# PaxInstrument-T400.net
KiCad netlist of a schematic drawn in EAGLE
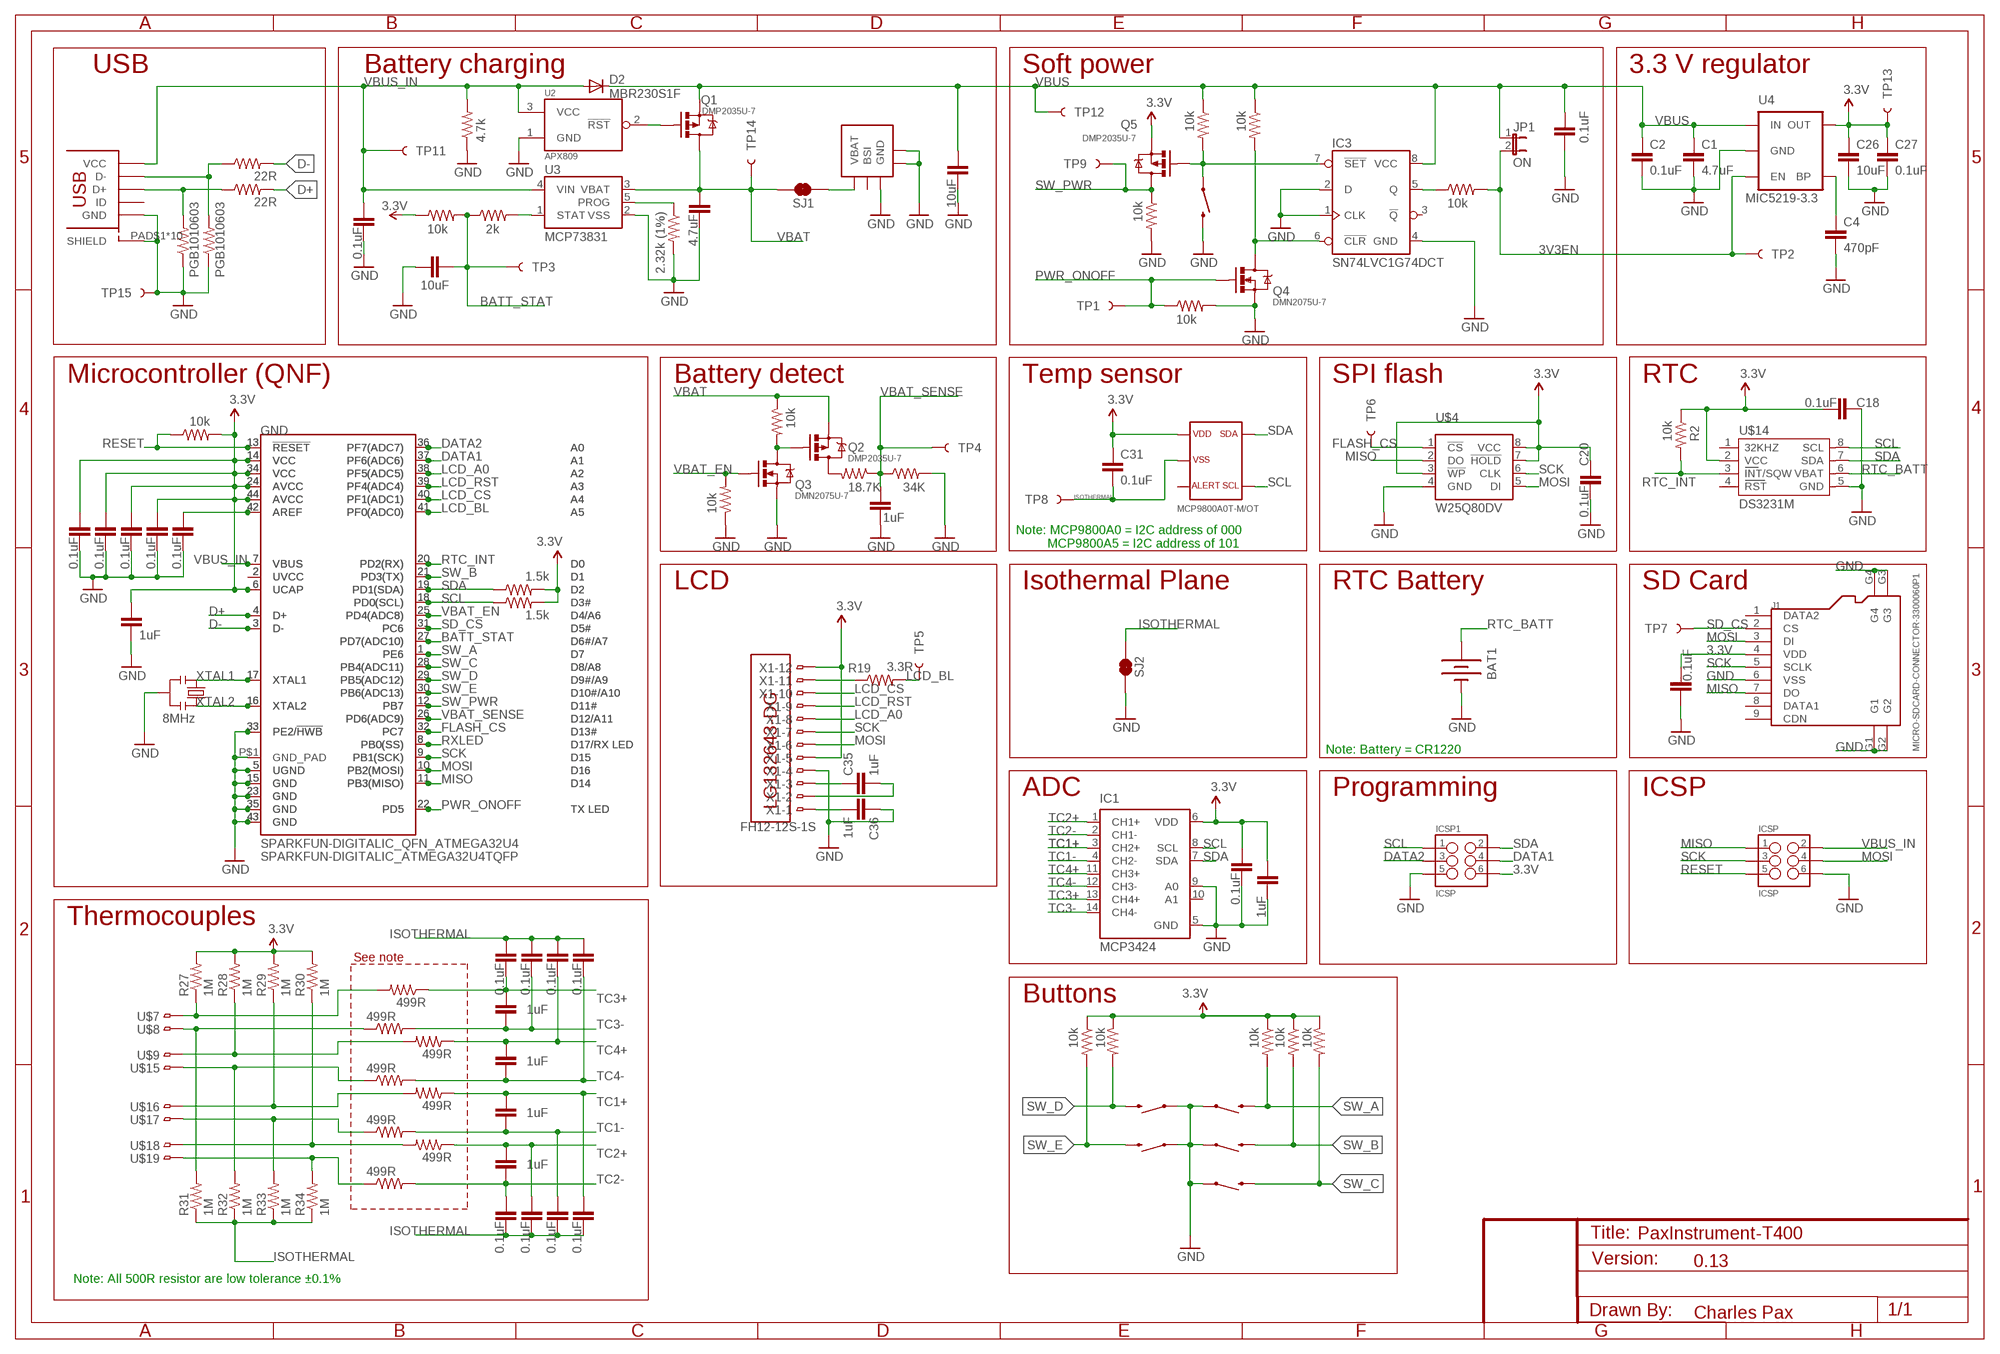
[diagram p0: schematic, sheet 1]

(export (version "E")
  (design (tool "Eeschema 10.0.6"))
  (components
    (comp (ref "BAT1")
      (value "BATTERY12MM")
      (footprint "eagle-import:BATTCON_12MM")
      (fields (field (name "MF") "Keystone Electronics") (field (name "MPN") "3000TR"))
      (libsource (lib "eagle-import") (part "BATTERY12MM"))
    )
    (comp (ref "C1")
      (value "4.7uF")
      (footprint "eagle-import:SPARKFUN-CAPACITORS_0603-CAP")
      (libsource (lib "eagle-import") (part "SPARKFUN-CAPACITORS_CAP0603-CAP"))
    )
    (comp (ref "C2")
      (value "0.1uF")
      (footprint "eagle-import:SPARKFUN-CAPACITORS_0603-CAP")
      (libsource (lib "eagle-import") (part "SPARKFUN-CAPACITORS_CAP0603-CAP"))
    )
    (comp (ref "C3")
      (value "0.1uF")
      (footprint "eagle-import:SPARKFUN-CAPACITORS_0603-CAP")
      (libsource (lib "eagle-import") (part "SPARKFUN-CAPACITORS_CAP0603-CAP"))
    )
    (comp (ref "C4")
      (value "470pF")
      (footprint "eagle-import:SPARKFUN-CAPACITORS_0603-CAP")
      (libsource (lib "eagle-import") (part "SPARKFUN-CAPACITORS_CAP0603-CAP"))
    )
    (comp (ref "C5")
      (value "0.1uF")
      (footprint "eagle-import:SPARKFUN-CAPACITORS_0603-CAP")
      (libsource (lib "eagle-import") (part "SPARKFUN-CAPACITORS_CAP0603-CAP"))
    )
    (comp (ref "C6")
      (value "0.1uF")
      (footprint "eagle-import:SPARKFUN-CAPACITORS_0603-CAP")
      (libsource (lib "eagle-import") (part "SPARKFUN-CAPACITORS_CAP0603-CAP"))
    )
    (comp (ref "C7")
      (value "1uF")
      (footprint "eagle-import:SPARKFUN-CAPACITORS_0603-CAP")
      (libsource (lib "eagle-import") (part "SPARKFUN-CAPACITORS_CAP0603-CAP"))
    )
    (comp (ref "C8")
      (value "1uF")
      (footprint "eagle-import:SPARKFUN-CAPACITORS_0603-CAP")
      (libsource (lib "eagle-import") (part "SPARKFUN-CAPACITORS_CAP0603-CAP"))
    )
    (comp (ref "C9")
      (value "4.7uF")
      (footprint "eagle-import:SPARKFUN-CAPACITORS_0603-CAP")
      (libsource (lib "eagle-import") (part "SPARKFUN-CAPACITORS_CAP0603-CAP"))
    )
    (comp (ref "C10")
      (value "1uF")
      (footprint "eagle-import:SPARKFUN-CAPACITORS_0603-CAP")
      (libsource (lib "eagle-import") (part "SPARKFUN-CAPACITORS_CAP0603-CAP"))
    )
    (comp (ref "C11")
      (value "1uF")
      (footprint "eagle-import:SPARKFUN-CAPACITORS_0603-CAP")
      (libsource (lib "eagle-import") (part "SPARKFUN-CAPACITORS_CAP0603-CAP"))
    )
    (comp (ref "C12")
      (value "10uF")
      (footprint "eagle-import:SPARKFUN-CAPACITORS_0603-CAP")
      (libsource (lib "eagle-import") (part "SPARKFUN-CAPACITORS_CAP0603-CAP"))
    )
    (comp (ref "C13")
      (value "0.1uF")
      (footprint "eagle-import:SPARKFUN-CAPACITORS_0603-CAP")
      (libsource (lib "eagle-import") (part "SPARKFUN-CAPACITORS_CAP0603-CAP"))
    )
    (comp (ref "C14")
      (value "0.1uF")
      (footprint "eagle-import:SPARKFUN-CAPACITORS_0603-CAP")
      (libsource (lib "eagle-import") (part "SPARKFUN-CAPACITORS_CAP0603-CAP"))
    )
    (comp (ref "C15")
      (value "0.1uF")
      (footprint "eagle-import:SPARKFUN-CAPACITORS_0603-CAP")
      (libsource (lib "eagle-import") (part "SPARKFUN-CAPACITORS_CAP0603-CAP"))
    )
    (comp (ref "C16")
      (value "0.1uF")
      (footprint "eagle-import:SPARKFUN-CAPACITORS_0603-CAP")
      (libsource (lib "eagle-import") (part "SPARKFUN-CAPACITORS_CAP0603-CAP"))
    )
    (comp (ref "C17")
      (value "0.1uF")
      (footprint "eagle-import:SPARKFUN-CAPACITORS_0603-CAP")
      (libsource (lib "eagle-import") (part "SPARKFUN-CAPACITORS_CAP0603-CAP"))
    )
    (comp (ref "C18")
      (value "0.1uF")
      (footprint "eagle-import:SPARKFUN-CAPACITORS_0603-CAP")
      (libsource (lib "eagle-import") (part "SPARKFUN-CAPACITORS_CAP0603-CAP"))
    )
    (comp (ref "C19")
      (value "1uF")
      (footprint "eagle-import:SPARKFUN-CAPACITORS_0603-CAP")
      (libsource (lib "eagle-import") (part "SPARKFUN-CAPACITORS_CAP0603-CAP"))
    )
    (comp (ref "C20")
      (value "0.1uF")
      (footprint "eagle-import:SPARKFUN-CAPACITORS_0603-CAP")
      (libsource (lib "eagle-import") (part "SPARKFUN-CAPACITORS_CAP0603-CAP"))
    )
    (comp (ref "C21")
      (value "0.1uF")
      (footprint "eagle-import:SPARKFUN-CAPACITORS_0603-CAP")
      (libsource (lib "eagle-import") (part "SPARKFUN-CAPACITORS_CAP0603-CAP"))
    )
    (comp (ref "C22")
      (value "10uF")
      (footprint "eagle-import:SPARKFUN-CAPACITORS_0603-CAP")
      (libsource (lib "eagle-import") (part "SPARKFUN-CAPACITORS_CAP0603-CAP"))
    )
    (comp (ref "C23")
      (value "1uF")
      (footprint "eagle-import:SPARKFUN-CAPACITORS_0603-CAP")
      (libsource (lib "eagle-import") (part "SPARKFUN-CAPACITORS_CAP0603-CAP"))
    )
    (comp (ref "C24")
      (value "0.1uF")
      (footprint "eagle-import:SPARKFUN-CAPACITORS_0603-CAP")
      (libsource (lib "eagle-import") (part "SPARKFUN-CAPACITORS_CAP0603-CAP"))
    )
    (comp (ref "C25")
      (value "0.1uF")
      (footprint "eagle-import:SPARKFUN-CAPACITORS_0603-CAP")
      (libsource (lib "eagle-import") (part "SPARKFUN-CAPACITORS_CAP0603-CAP"))
    )
    (comp (ref "C26")
      (value "10uF")
      (footprint "eagle-import:SPARKFUN-CAPACITORS_0603-CAP")
      (libsource (lib "eagle-import") (part "SPARKFUN-CAPACITORS_CAP0603-CAP"))
    )
    (comp (ref "C27")
      (value "0.1uF")
      (footprint "eagle-import:SPARKFUN-CAPACITORS_0603-CAP")
      (libsource (lib "eagle-import") (part "SPARKFUN-CAPACITORS_CAP0603-CAP"))
    )
    (comp (ref "C28")
      (value "0.1uF")
      (footprint "eagle-import:SPARKFUN-CAPACITORS_0603-CAP")
      (libsource (lib "eagle-import") (part "SPARKFUN-CAPACITORS_CAP0603-CAP"))
    )
    (comp (ref "C29")
      (value "0.1uF")
      (footprint "eagle-import:SPARKFUN-CAPACITORS_0603-CAP")
      (libsource (lib "eagle-import") (part "SPARKFUN-CAPACITORS_CAP0603-CAP"))
    )
    (comp (ref "C30")
      (value "1uF")
      (footprint "eagle-import:SPARKFUN-CAPACITORS_0603-CAP")
      (libsource (lib "eagle-import") (part "SPARKFUN-CAPACITORS_CAP0603-CAP"))
    )
    (comp (ref "C31")
      (value "0.1uF")
      (footprint "eagle-import:SPARKFUN-CAPACITORS_0603-CAP")
      (libsource (lib "eagle-import") (part "SPARKFUN-CAPACITORS_CAP0603-CAP"))
    )
    (comp (ref "C32")
      (value "0.1uF")
      (footprint "eagle-import:SPARKFUN-CAPACITORS_0603-CAP")
      (libsource (lib "eagle-import") (part "SPARKFUN-CAPACITORS_CAP0603-CAP"))
    )
    (comp (ref "C33")
      (value "0.1uF")
      (footprint "eagle-import:SPARKFUN-CAPACITORS_0603-CAP")
      (libsource (lib "eagle-import") (part "SPARKFUN-CAPACITORS_CAP0603-CAP"))
    )
    (comp (ref "C34")
      (value "0.1uF")
      (footprint "eagle-import:SPARKFUN-CAPACITORS_0603-CAP")
      (libsource (lib "eagle-import") (part "SPARKFUN-CAPACITORS_CAP0603-CAP"))
    )
    (comp (ref "C35")
      (value "1uF")
      (footprint "eagle-import:SPARKFUN-CAPACITORS_0603-CAP")
      (libsource (lib "eagle-import") (part "SPARKFUN-CAPACITORS_CAP0603-CAP"))
    )
    (comp (ref "C36")
      (value "1uF")
      (footprint "eagle-import:SPARKFUN-CAPACITORS_0603-CAP")
      (libsource (lib "eagle-import") (part "SPARKFUN-CAPACITORS_CAP0603-CAP"))
    )
    (comp (ref "C37")
      (value "0.1uF")
      (footprint "eagle-import:SPARKFUN-CAPACITORS_0603-CAP")
      (libsource (lib "eagle-import") (part "SPARKFUN-CAPACITORS_CAP0603-CAP"))
    )
    (comp (ref "D2")
      (value "MBR230S1F")
      (footprint "eagle-import:SOD123")
      (fields (field (name "MF") "DIODES INC") (field (name "MPN") "MBR230S1F-7"))
      (libsource (lib "eagle-import") (part "SPARKFUN-DISCRETESEMI_DIODESOD123SOD123"))
    )
    (comp (ref "GND")
      (value "SPARKFUN-DIGITALIC_QFN_ATMEGA32U4")
      (footprint "eagle-import:SPARKFUN-DIGITALIC_SPARKFUN-DIGITALIC_QFN-44")
      (fields (field (name "MF") "Atmel") (field (name "MPN") "ATMEGA32U4-MU"))
      (libsource (lib "eagle-import") (part "SPARKFUN-DIGITALIC_QFN_ATMEGA32U4"))
    )
    (comp (ref "IC1")
      (value "MCP3424")
      (footprint "eagle-import:SO14")
      (fields (field (name "MF") "Microchip Technology") (field (name "MPN") "MCP3424-E/SL"))
      (libsource (lib "eagle-import") (part "MCP3424"))
    )
    (comp (ref "IC3")
      (value "SN74LVC1G74DCT")
      (footprint "eagle-import:SSOP8")
      (fields (field (name "MF") "Texas Instruments") (field (name "MPN") "SN74LVC1G74DCTR "))
      (libsource (lib "eagle-import") (part "SN74LVC1G74DCT"))
    )
    (comp (ref "ICSP")
      (value "ICSP")
      (footprint "eagle-import:SPARKFUN-CONNECTORS_2X3_SMT_POSTS_PAXINSTRUMENT")
      (fields (field (name "MF") "FCI") (field (name "MPN") "95278-101A06LF"))
      (libsource (lib "eagle-import") (part "SPARKFUN-CONNECTORS_M03X2PAX"))
    )
    (comp (ref "ICSP1")
      (value "ICSP")
      (footprint "eagle-import:SPARKFUN-CONNECTORS_2X3_SMT_POSTS_PAXINSTRUMENT")
      (fields (field (name "MF") "FCI") (field (name "MPN") "95278-101A06LF"))
      (libsource (lib "eagle-import") (part "SPARKFUN-CONNECTORS_M03X2PAX"))
    )
    (comp (ref "J1")
      (value "MICRO-SDCARD-CONNECTOR-3300060P1")
      (footprint "eagle-import:9P-SMD-W-RING")
      (fields (field (name "MF") "SUNTECH") (field (name "MPN") "ST-TF-003A"))
      (libsource (lib "eagle-import") (part "MICRO-SDCARD-CONNECTOR-3300060P1"))
    )
    (comp (ref "JP1")
      (value "ON")
      (footprint "eagle-import:SJ_2S-NO")
      (libsource (lib "eagle-import") (part "JUMPER-2SMD-NO"))
    )
    (comp (ref "Q1")
      (value "DMP2035U-7")
      (footprint "eagle-import:SOT23")
      (fields (field (name "MF") "DIODES INC"))
      (libsource (lib "eagle-import") (part "MOSFET-PCHANNELSMT"))
    )
    (comp (ref "Q2")
      (value "DMP2035U-7")
      (footprint "eagle-import:SOT23")
      (fields (field (name "MF") "DIODES INC"))
      (libsource (lib "eagle-import") (part "MOSFET-PCHANNELSMT"))
    )
    (comp (ref "Q3")
      (value "DMN2075U-7")
      (footprint "eagle-import:SOT23")
      (fields (field (name "MF") "DIODES INC") (field (name "MPN") "DMN2075U-7 "))
      (libsource (lib "eagle-import") (part "MOSFET-NCHANNELSMT"))
    )
    (comp (ref "Q4")
      (value "DMN2075U-7")
      (footprint "eagle-import:SOT23")
      (fields (field (name "MF") "DIODES INC") (field (name "MPN") "DMN2075U-7 "))
      (libsource (lib "eagle-import") (part "MOSFET-NCHANNELSMT"))
    )
    (comp (ref "Q5")
      (value "DMP2035U-7")
      (footprint "eagle-import:SOT23")
      (fields (field (name "MF") "DIODES INC"))
      (libsource (lib "eagle-import") (part "MOSFET-PCHANNELSMT"))
    )
    (comp (ref "R1")
      (value "10k")
      (footprint "eagle-import:SPARKFUN-RESISTORS_0603-RES")
      (libsource (lib "eagle-import") (part "SPARKFUN-RESISTORS_RESISTOR0603-RES"))
    )
    (comp (ref "R2")
      (value "10k")
      (footprint "eagle-import:SPARKFUN-RESISTORS_0603-RES")
      (libsource (lib "eagle-import") (part "SPARKFUN-RESISTORS_RESISTOR0603-RES"))
    )
    (comp (ref "R3")
      (value "2.32k (1%)")
      (footprint "eagle-import:SPARKFUN-RESISTORS_0603-RES")
      (libsource (lib "eagle-import") (part "SPARKFUN-RESISTORS_RESISTOR0603-RES"))
    )
    (comp (ref "R4")
      (value "10k")
      (footprint "eagle-import:SPARKFUN-RESISTORS_0603-RES")
      (libsource (lib "eagle-import") (part "SPARKFUN-RESISTORS_RESISTOR0603-RES"))
    )
    (comp (ref "R5")
      (value "10k")
      (footprint "eagle-import:SPARKFUN-RESISTORS_0603-RES")
      (libsource (lib "eagle-import") (part "SPARKFUN-RESISTORS_RESISTOR0603-RES"))
    )
    (comp (ref "R6")
      (value "10k")
      (footprint "eagle-import:SPARKFUN-RESISTORS_0603-RES")
      (libsource (lib "eagle-import") (part "SPARKFUN-RESISTORS_RESISTOR0603-RES"))
    )
    (comp (ref "R7")
      (value "10k")
      (footprint "eagle-import:SPARKFUN-RESISTORS_0603-RES")
      (libsource (lib "eagle-import") (part "SPARKFUN-RESISTORS_RESISTOR0603-RES"))
    )
    (comp (ref "R8")
      (value "10k")
      (footprint "eagle-import:SPARKFUN-RESISTORS_0603-RES")
      (libsource (lib "eagle-import") (part "SPARKFUN-RESISTORS_RESISTOR0603-RES"))
    )
    (comp (ref "R9")
      (value "22R")
      (footprint "eagle-import:SPARKFUN-RESISTORS_0603-RES")
      (libsource (lib "eagle-import") (part "SPARKFUN-RESISTORS_RESISTOR0603-RES"))
    )
    (comp (ref "R10")
      (value "22R")
      (footprint "eagle-import:SPARKFUN-RESISTORS_0603-RES")
      (libsource (lib "eagle-import") (part "SPARKFUN-RESISTORS_RESISTOR0603-RES"))
    )
    (comp (ref "R11")
      (value "10k")
      (footprint "eagle-import:SPARKFUN-RESISTORS_0603-RES")
      (libsource (lib "eagle-import") (part "SPARKFUN-RESISTORS_RESISTOR0603-RES"))
    )
    (comp (ref "R12")
      (value "10k")
      (footprint "eagle-import:SPARKFUN-RESISTORS_0603-RES")
      (libsource (lib "eagle-import") (part "SPARKFUN-RESISTORS_RESISTOR0603-RES"))
    )
    (comp (ref "R13")
      (value "1.5k")
      (footprint "eagle-import:SPARKFUN-RESISTORS_0603-RES")
      (libsource (lib "eagle-import") (part "SPARKFUN-RESISTORS_RESISTOR0603-RES"))
    )
    (comp (ref "R14")
      (value "1.5k")
      (footprint "eagle-import:SPARKFUN-RESISTORS_0603-RES")
      (libsource (lib "eagle-import") (part "SPARKFUN-RESISTORS_RESISTOR0603-RES"))
    )
    (comp (ref "R15")
      (value "10k")
      (footprint "eagle-import:SPARKFUN-RESISTORS_0603-RES")
      (libsource (lib "eagle-import") (part "SPARKFUN-RESISTORS_RESISTOR0603-RES"))
    )
    (comp (ref "R16")
      (value "10k")
      (footprint "eagle-import:SPARKFUN-RESISTORS_0603-RES")
      (libsource (lib "eagle-import") (part "SPARKFUN-RESISTORS_RESISTOR0603-RES"))
    )
    (comp (ref "R17")
      (value "2k")
      (footprint "eagle-import:SPARKFUN-RESISTORS_0603-RES")
      (libsource (lib "eagle-import") (part "SPARKFUN-RESISTORS_RESISTOR0603-RES"))
    )
    (comp (ref "R18")
      (value "10k")
      (footprint "eagle-import:SPARKFUN-RESISTORS_0603-RES")
      (libsource (lib "eagle-import") (part "SPARKFUN-RESISTORS_RESISTOR0603-RES"))
    )
    (comp (ref "R19")
      (value "3.3R")
      (footprint "eagle-import:SPARKFUN-RESISTORS_0603-RES")
      (libsource (lib "eagle-import") (part "SPARKFUN-RESISTORS_RESISTOR0603-RES"))
    )
    (comp (ref "R20")
      (value "18.7K")
      (footprint "eagle-import:SPARKFUN-RESISTORS_0603-RES")
      (libsource (lib "eagle-import") (part "SPARKFUN-RESISTORS_RESISTOR0603-RES"))
    )
    (comp (ref "R21")
      (value "10k")
      (footprint "eagle-import:SPARKFUN-RESISTORS_0603-RES")
      (libsource (lib "eagle-import") (part "SPARKFUN-RESISTORS_RESISTOR0603-RES"))
    )
    (comp (ref "R22")
      (value "10k")
      (footprint "eagle-import:SPARKFUN-RESISTORS_0603-RES")
      (libsource (lib "eagle-import") (part "SPARKFUN-RESISTORS_RESISTOR0603-RES"))
    )
    (comp (ref "R23")
      (value "10k")
      (footprint "eagle-import:SPARKFUN-RESISTORS_0603-RES")
      (libsource (lib "eagle-import") (part "SPARKFUN-RESISTORS_RESISTOR0603-RES"))
    )
    (comp (ref "R24")
      (value "34K")
      (footprint "eagle-import:SPARKFUN-RESISTORS_0603-RES")
      (libsource (lib "eagle-import") (part "SPARKFUN-RESISTORS_RESISTOR0603-RES"))
    )
    (comp (ref "R25")
      (value "4.7k")
      (footprint "eagle-import:SPARKFUN-RESISTORS_0603-RES")
      (libsource (lib "eagle-import") (part "SPARKFUN-RESISTORS_RESISTOR0603-RES"))
    )
    (comp (ref "R27")
      (value "1M")
      (footprint "eagle-import:SPARKFUN-RESISTORS_0603-RES")
      (libsource (lib "eagle-import") (part "SPARKFUN-RESISTORS_RESISTOR0603-RES"))
    )
    (comp (ref "R28")
      (value "1M")
      (footprint "eagle-import:SPARKFUN-RESISTORS_0603-RES")
      (libsource (lib "eagle-import") (part "SPARKFUN-RESISTORS_RESISTOR0603-RES"))
    )
    (comp (ref "R29")
      (value "1M")
      (footprint "eagle-import:SPARKFUN-RESISTORS_0603-RES")
      (libsource (lib "eagle-import") (part "SPARKFUN-RESISTORS_RESISTOR0603-RES"))
    )
    (comp (ref "R30")
      (value "1M")
      (footprint "eagle-import:SPARKFUN-RESISTORS_0603-RES")
      (libsource (lib "eagle-import") (part "SPARKFUN-RESISTORS_RESISTOR0603-RES"))
    )
    (comp (ref "R31")
      (value "1M")
      (footprint "eagle-import:SPARKFUN-RESISTORS_0603-RES")
      (libsource (lib "eagle-import") (part "SPARKFUN-RESISTORS_RESISTOR0603-RES"))
    )
    (comp (ref "R32")
      (value "1M")
      (footprint "eagle-import:SPARKFUN-RESISTORS_0603-RES")
      (libsource (lib "eagle-import") (part "SPARKFUN-RESISTORS_RESISTOR0603-RES"))
    )
    (comp (ref "R33")
      (value "1M")
      (footprint "eagle-import:SPARKFUN-RESISTORS_0603-RES")
      (libsource (lib "eagle-import") (part "SPARKFUN-RESISTORS_RESISTOR0603-RES"))
    )
    (comp (ref "R34")
      (value "1M")
      (footprint "eagle-import:SPARKFUN-RESISTORS_0603-RES")
      (libsource (lib "eagle-import") (part "SPARKFUN-RESISTORS_RESISTOR0603-RES"))
    )
    (comp (ref "R35")
      (value "499R")
      (footprint "eagle-import:SPARKFUN-RESISTORS_0603-RES")
      (fields (field (name "MF") "Vishay") (field (name "MPN") "TNPW0603499RBEEA"))
      (libsource (lib "eagle-import") (part "SPARKFUN-RESISTORS_RESISTOR0603-RES"))
    )
    (comp (ref "R36")
      (value "499R")
      (footprint "eagle-import:SPARKFUN-RESISTORS_0603-RES")
      (fields (field (name "MF") "Vishay") (field (name "MPN") "TNPW0603499RBEEA"))
      (libsource (lib "eagle-import") (part "SPARKFUN-RESISTORS_RESISTOR0603-RES"))
    )
    (comp (ref "R37")
      (value "499R")
      (footprint "eagle-import:SPARKFUN-RESISTORS_0603-RES")
      (fields (field (name "MF") "Vishay") (field (name "MPN") "TNPW0603499RBEEA"))
      (libsource (lib "eagle-import") (part "SPARKFUN-RESISTORS_RESISTOR0603-RES"))
    )
    (comp (ref "R38")
      (value "499R")
      (footprint "eagle-import:SPARKFUN-RESISTORS_0603-RES")
      (fields (field (name "MF") "Vishay") (field (name "MPN") "TNPW0603499RBEEA"))
      (libsource (lib "eagle-import") (part "SPARKFUN-RESISTORS_RESISTOR0603-RES"))
    )
    (comp (ref "R39")
      (value "499R")
      (footprint "eagle-import:SPARKFUN-RESISTORS_0603-RES")
      (fields (field (name "MF") "Vishay") (field (name "MPN") "TNPW0603499RBEEA"))
      (libsource (lib "eagle-import") (part "SPARKFUN-RESISTORS_RESISTOR0603-RES"))
    )
    (comp (ref "R40")
      (value "499R")
      (footprint "eagle-import:SPARKFUN-RESISTORS_0603-RES")
      (fields (field (name "MF") "Vishay") (field (name "MPN") "TNPW0603499RBEEA"))
      (libsource (lib "eagle-import") (part "SPARKFUN-RESISTORS_RESISTOR0603-RES"))
    )
    (comp (ref "R41")
      (value "499R")
      (footprint "eagle-import:SPARKFUN-RESISTORS_0603-RES")
      (fields (field (name "MF") "Vishay") (field (name "MPN") "TNPW0603499RBEEA"))
      (libsource (lib "eagle-import") (part "SPARKFUN-RESISTORS_RESISTOR0603-RES"))
    )
    (comp (ref "R42")
      (value "499R")
      (footprint "eagle-import:SPARKFUN-RESISTORS_0603-RES")
      (fields (field (name "MF") "Vishay") (field (name "MPN") "TNPW0603499RBEEA"))
      (libsource (lib "eagle-import") (part "SPARKFUN-RESISTORS_RESISTOR0603-RES"))
    )
    (comp (ref "S1")
      (value "SWITCH-MOMENTARY-2SMD")
      (footprint "eagle-import:TACTILE_SWITCH_SMD")
      (fields (field (name "MF") "C&K Components") (field (name "MPN") "RS-187R05A2-DS MT RT"))
      (libsource (lib "eagle-import") (part "SWITCH-MOMENTARY-2SMD"))
    )
    (comp (ref "S2")
      (value "SWITCH-MOMENTARY-2SMD")
      (footprint "eagle-import:TACTILE_SWITCH_SMD")
      (fields (field (name "MF") "C&K Components") (field (name "MPN") "RS-187R05A2-DS MT RT"))
      (libsource (lib "eagle-import") (part "SWITCH-MOMENTARY-2SMD"))
    )
    (comp (ref "S3")
      (value "SWITCH-MOMENTARY-2SMD")
      (footprint "eagle-import:TACTILE_SWITCH_SMD")
      (fields (field (name "MF") "C&K Components") (field (name "MPN") "RS-187R05A2-DS MT RT"))
      (libsource (lib "eagle-import") (part "SWITCH-MOMENTARY-2SMD"))
    )
    (comp (ref "S4")
      (value "SWITCH-MOMENTARY-2SMD")
      (footprint "eagle-import:TACTILE_SWITCH_SMD")
      (fields (field (name "MF") "C&K Components") (field (name "MPN") "RS-187R05A2-DS MT RT"))
      (libsource (lib "eagle-import") (part "SWITCH-MOMENTARY-2SMD"))
    )
    (comp (ref "S5")
      (value "SWITCH-MOMENTARY-2SMD")
      (footprint "eagle-import:TACTILE_SWITCH_SMD")
      (fields (field (name "MF") "C&K Components") (field (name "MPN") "RS-187R05A2-DS MT RT"))
      (libsource (lib "eagle-import") (part "SWITCH-MOMENTARY-2SMD"))
    )
    (comp (ref "S6")
      (value "SWITCH-MOMENTARY-2SMD")
      (footprint "eagle-import:TACTILE_SWITCH_SMD")
      (fields (field (name "MF") "C&K Components") (field (name "MPN") "RS-187R05A2-DS MT RT"))
      (libsource (lib "eagle-import") (part "SWITCH-MOMENTARY-2SMD"))
    )
    (comp (ref "SJ1")
      (value "JUMPER-PAD-2-NC_BY_TRACE")
      (footprint "eagle-import:PAD-JUMPER-2-NC_BY_TRACE_YES_SILK")
      (libsource (lib "eagle-import") (part "JUMPER-PAD-2-NC_BY_TRACE"))
    )
    (comp (ref "SJ2")
      (value "JUMPER-PAD-2-NC_BY_TRACE")
      (footprint "eagle-import:PAD-JUMPER-2-NC_BY_TRACE_YES_SILK")
      (libsource (lib "eagle-import") (part "JUMPER-PAD-2-NC_BY_TRACE"))
    )
    (comp (ref "TP1")
      (value "PWR_ONOFF")
      (footprint "eagle-import:TP_15TH")
      (libsource (lib "eagle-import") (part "TEST-POINTTP_15TH_THRU"))
    )
    (comp (ref "TP2")
      (value "3V3_EN")
      (footprint "eagle-import:TP_15TH")
      (libsource (lib "eagle-import") (part "TEST-POINTTP_15TH_THRU"))
    )
    (comp (ref "TP3")
      (value "BATT_STAT")
      (footprint "eagle-import:TP_15TH")
      (libsource (lib "eagle-import") (part "TEST-POINTTP_15TH_THRU"))
    )
    (comp (ref "TP4")
      (value "VBAT_SENSE")
      (footprint "eagle-import:TP_15TH")
      (libsource (lib "eagle-import") (part "TEST-POINTTP_15TH_THRU"))
    )
    (comp (ref "TP5")
      (value "LCD_BL")
      (footprint "eagle-import:TP_15TH")
      (libsource (lib "eagle-import") (part "TEST-POINTTP_15TH_THRU"))
    )
    (comp (ref "TP6")
      (value "FLASH_CS")
      (footprint "eagle-import:TP_15TH")
      (libsource (lib "eagle-import") (part "TEST-POINTTP_15TH_THRU"))
    )
    (comp (ref "TP7")
      (value "SD_CS")
      (footprint "eagle-import:TP_15TH")
      (libsource (lib "eagle-import") (part "TEST-POINTTP_15TH_THRU"))
    )
    (comp (ref "TP8")
      (value "ISOTHERMAL")
      (footprint "eagle-import:TP_15TH")
      (libsource (lib "eagle-import") (part "TEST-POINTTP_15TH_THRU"))
    )
    (comp (ref "TP9")
      (value "SW_PWR")
      (footprint "eagle-import:TP_15TH")
      (libsource (lib "eagle-import") (part "TEST-POINTTP_15TH_THRU"))
    )
    (comp (ref "TP11")
      (value "VBUS_IN")
      (footprint "eagle-import:TP_15TH")
      (libsource (lib "eagle-import") (part "TEST-POINTTP_15TH_THRU"))
    )
    (comp (ref "TP12")
      (value "VBUS")
      (footprint "eagle-import:TP_15TH")
      (libsource (lib "eagle-import") (part "TEST-POINTTP_15TH_THRU"))
    )
    (comp (ref "TP13")
      (value "3.3V")
      (footprint "eagle-import:TP_15TH")
      (libsource (lib "eagle-import") (part "TEST-POINTTP_15TH_THRU"))
    )
    (comp (ref "TP14")
      (value "VBAT")
      (footprint "eagle-import:TP_15TH")
      (libsource (lib "eagle-import") (part "TEST-POINTTP_15TH_THRU"))
    )
    (comp (ref "TP15")
      (value "GND")
      (footprint "eagle-import:TP_15TH")
      (libsource (lib "eagle-import") (part "TEST-POINTTP_15TH_THRU"))
    )
    (comp (ref "U$1")
      (value "USB_MICROSMT+THRUHULE")
      (footprint "eagle-import:USB_MICRO_THRUHOLE")
      (fields (field (name "MF") "FCI") (field (name "MPN") "10118194-0001LF"))
      (libsource (lib "eagle-import") (part "USB_MICROSMT+THRUHULE"))
    )
    (comp (ref "U$2")
      (value "BL-5C-CONNECTOR")
      (footprint "eagle-import:BL-5C-CONNECTOR")
      (fields (field (name "MPN") "BC-4-3P (77H)"))
      (libsource (lib "eagle-import") (part "BL-5C-CONNECTOR"))
    )
    (comp (ref "U$3")
      (value "SPARKFUN-DIGITALIC_ATMEGA32U4TQFP")
      (footprint "eagle-import:SPARKFUN-DIGITALIC_SPARKFUN-DIGITALIC_TQFP44")
      (fields (field (name "MF") "Atmel") (field (name "MPN") "ATMEGA32U4-AU"))
      (libsource (lib "eagle-import") (part "SPARKFUN-DIGITALIC_ATMEGA32U4TQFP"))
    )
    (comp (ref "U$4")
      (value "W25Q80DV")
      (footprint "eagle-import:CHARLESPAX_SOIC8M")
      (fields (field (name "MF") "Winbond Electronics") (field (name "MPN") "W25Q80DVSSIG-ND"))
      (libsource (lib "eagle-import") (part "W25Q80BV"))
    )
    (comp (ref "U$5")
      (value "LG132643-DG")
      (footprint "eagle-import:LG132643-DG")
      (fields (field (name "MPN") "LG132643-DW"))
      (libsource (lib "eagle-import") (part "LG132643-DG"))
    )
    (comp (ref "U$7")
      (value "TC-MINI-SINGLE")
      (footprint "eagle-import:TC-CLIP-SINGLE")
      (fields (field (name "MF") "Pax Instrument") (field (name "MPN") "Thermo-clip2"))
      (libsource (lib "eagle-import") (part "TC-MINI-SINGLE"))
    )
    (comp (ref "U$8")
      (value "TC-MINI-SINGLE")
      (footprint "eagle-import:TC-CLIP-SINGLE")
      (fields (field (name "MF") "Pax Instrument") (field (name "MPN") "Thermo-clip2"))
      (libsource (lib "eagle-import") (part "TC-MINI-SINGLE"))
    )
    (comp (ref "U$9")
      (value "TC-MINI-SINGLE")
      (footprint "eagle-import:TC-CLIP-SINGLE")
      (fields (field (name "MF") "Pax Instrument") (field (name "MPN") "Thermo-clip2"))
      (libsource (lib "eagle-import") (part "TC-MINI-SINGLE"))
    )
    (comp (ref "U$14")
      (value "DS3231M")
      (footprint "eagle-import:SOIC8")
      (fields (field (name "MF") "Maxim Integrated") (field (name "MPN") "DS3231MZ+"))
      (libsource (lib "eagle-import") (part "DS3231M"))
    )
    (comp (ref "U$15")
      (value "TC-MINI-SINGLE")
      (footprint "eagle-import:TC-CLIP-SINGLE")
      (fields (field (name "MF") "Pax Instrument") (field (name "MPN") "Thermo-clip2"))
      (libsource (lib "eagle-import") (part "TC-MINI-SINGLE"))
    )
    (comp (ref "U$16")
      (value "TC-MINI-SINGLE")
      (footprint "eagle-import:TC-CLIP-SINGLE")
      (fields (field (name "MF") "Pax Instrument") (field (name "MPN") "Thermo-clip2"))
      (libsource (lib "eagle-import") (part "TC-MINI-SINGLE"))
    )
    (comp (ref "U$17")
      (value "TC-MINI-SINGLE")
      (footprint "eagle-import:TC-CLIP-SINGLE")
      (fields (field (name "MF") "Pax Instrument") (field (name "MPN") "Thermo-clip2"))
      (libsource (lib "eagle-import") (part "TC-MINI-SINGLE"))
    )
    (comp (ref "U$18")
      (value "TC-MINI-SINGLE")
      (footprint "eagle-import:TC-CLIP-SINGLE")
      (fields (field (name "MF") "Pax Instrument") (field (name "MPN") "Thermo-clip2"))
      (libsource (lib "eagle-import") (part "TC-MINI-SINGLE"))
    )
    (comp (ref "U$19")
      (value "TC-MINI-SINGLE")
      (footprint "eagle-import:TC-CLIP-SINGLE")
      (fields (field (name "MF") "Pax Instrument") (field (name "MPN") "Thermo-clip2"))
      (libsource (lib "eagle-import") (part "TC-MINI-SINGLE"))
    )
    (comp (ref "U1")
      (value "MCP9800")
      (footprint "eagle-import:SOT23-5L")
      (fields (field (name "MF") "Microchip Technology") (field (name "MPN") "MCP9800A0T-M/OT"))
      (libsource (lib "eagle-import") (part "MCP9800"))
    )
    (comp (ref "U2")
      (value "APX809")
      (footprint "eagle-import:SOT23")
      (fields (field (name "MF") "DIODES INC") (field (name "MPN") "APX809-44SAG-7"))
      (libsource (lib "eagle-import") (part "APX809"))
    )
    (comp (ref "U3")
      (value "MCP73831")
      (footprint "eagle-import:SOT23-5")
      (fields (field (name "MF") "Microchip Technology") (field (name "MPN") "MCP73832T-2DCI/OT"))
      (libsource (lib "eagle-import") (part "MCP73831"))
    )
    (comp (ref "U4")
      (value "MIC5219-3.3V")
      (footprint "eagle-import:SOT23-5")
      (fields (field (name "MF") "Micrel") (field (name "MPN") "MIC5219-3.3YM5 TR"))
      (libsource (lib "eagle-import") (part "V_REG_LDOSMD"))
    )
    (comp (ref "X1")
      (value "FH12-12S-1S")
      (footprint "eagle-import:FH12-12S-1SH")
      (fields (field (name "MF") "Hirose Connector") (field (name "MPN") "FH12-12S-1SH(55)"))
      (libsource (lib "eagle-import") (part "FH12-12S-1S"))
    )
    (comp (ref "Y1")
      (value "RESONATORSMD")
      (footprint "eagle-import:RESONATOR-SMD")
      (fields (field (name "MF") "Murata Electronics") (field (name "MPN") "CSTCE8M00G52-R0"))
      (libsource (lib "eagle-import") (part "RESONATORSMD"))
    )
    (comp (ref "Z1")
      (value "PGB1010603")
      (footprint "eagle-import:SPARKFUN-RESISTORS_0603-RES")
      (fields (field (name "MF") "Littelfuse") (field (name "MPN") "PGB1010603NRHF"))
      (libsource (lib "eagle-import") (part "SPARKFUN-RESISTORS_RESISTOR0603-RES"))
    )
    (comp (ref "Z2")
      (value "PGB1010603")
      (footprint "eagle-import:SPARKFUN-RESISTORS_0603-RES")
      (fields (field (name "MF") "Littelfuse") (field (name "MPN") "PGB1010603NRHF"))
      (libsource (lib "eagle-import") (part "SPARKFUN-RESISTORS_RESISTOR0603-RES"))
    )
  )
  (nets
    (net (code "1") (name "/3V3EN") (class "Default")
      (node (ref "JP1") (pin "2") (pinfunction "2_2") (pintype "passive"))
      (node (ref "R21") (pin "2") (pinfunction "2_2") (pintype "passive"))
      (node (ref "TP2") (pin "P$1") (pinfunction "1_P$1") (pintype "bidirectional"))
      (node (ref "U4") (pin "3") (pinfunction "EN_3") (pintype "input"))
    )
    (net (code "2") (name "/BATT_STAT") (class "Default")
      (node (ref "C22") (pin "1") (pinfunction "1_1") (pintype "passive"))
      (node (ref "GND") (pin "27") (pinfunction "PD7(ADC10)_27") (pintype "bidirectional"))
      (node (ref "R1") (pin "2") (pinfunction "2_2") (pintype "passive"))
      (node (ref "R17") (pin "1") (pinfunction "1_1") (pintype "passive"))
      (node (ref "TP3") (pin "P$1") (pinfunction "1_P$1") (pintype "bidirectional"))
      (node (ref "U$3") (pin "27") (pinfunction "PD7(ADC10)_27") (pintype "bidirectional"))
    )
    (net (code "3") (name "/DATA1") (class "Default")
      (node (ref "GND") (pin "37") (pinfunction "PF6(ADC6)_37") (pintype "bidirectional"))
      (node (ref "ICSP1") (pin "4") (pinfunction "4_4") (pintype "bidirectional"))
      (node (ref "U$3") (pin "37") (pinfunction "PF6(ADC6)_37") (pintype "bidirectional"))
    )
    (net (code "4") (name "/DATA2") (class "Default")
      (node (ref "GND") (pin "36") (pinfunction "PF7(ADC7)_36") (pintype "bidirectional"))
      (node (ref "ICSP1") (pin "3") (pinfunction "3_3") (pintype "bidirectional"))
      (node (ref "U$3") (pin "36") (pinfunction "PF7(ADC7)_36") (pintype "bidirectional"))
    )
    (net (code "5") (name "/FLASH_CS") (class "Default")
      (node (ref "GND") (pin "32") (pinfunction "PC7_32") (pintype "bidirectional"))
      (node (ref "TP6") (pin "P$1") (pinfunction "1_P$1") (pintype "bidirectional"))
      (node (ref "U$3") (pin "32") (pinfunction "PC7_32") (pintype "bidirectional"))
      (node (ref "U$4") (pin "1") (pinfunction "~{CS}_1") (pintype "bidirectional"))
    )
    (net (code "6") (name "/ISOTHERMAL") (class "Default")
      (node (ref "C13") (pin "2") (pinfunction "2_2") (pintype "passive"))
      (node (ref "C14") (pin "2") (pinfunction "2_2") (pintype "passive"))
      (node (ref "C15") (pin "2") (pinfunction "2_2") (pintype "passive"))
      (node (ref "C16") (pin "2") (pinfunction "2_2") (pintype "passive"))
      (node (ref "C17") (pin "1") (pinfunction "1_1") (pintype "passive"))
      (node (ref "C24") (pin "1") (pinfunction "1_1") (pintype "passive"))
      (node (ref "C25") (pin "1") (pinfunction "1_1") (pintype "passive"))
      (node (ref "C31") (pin "2") (pinfunction "2_2") (pintype "passive"))
      (node (ref "C37") (pin "1") (pinfunction "1_1") (pintype "passive"))
      (node (ref "R31") (pin "1") (pinfunction "1_1") (pintype "passive"))
      (node (ref "R32") (pin "1") (pinfunction "1_1") (pintype "passive"))
      (node (ref "R33") (pin "1") (pinfunction "1_1") (pintype "passive"))
      (node (ref "R34") (pin "1") (pinfunction "1_1") (pintype "passive"))
      (node (ref "SJ2") (pin "2") (pinfunction "2_2") (pintype "passive"))
      (node (ref "TP8") (pin "P$1") (pinfunction "1_P$1") (pintype "bidirectional"))
      (node (ref "U1") (pin "2") (pinfunction "2_2") (pintype "bidirectional"))
    )
    (net (code "7") (name "/LCD_A0") (class "Default")
      (node (ref "GND") (pin "38") (pinfunction "PF5(ADC5)_38") (pintype "bidirectional"))
      (node (ref "U$3") (pin "38") (pinfunction "PF5(ADC5)_38") (pintype "bidirectional"))
      (node (ref "X1") (pin "8") (pinfunction "1_8") (pintype "passive"))
    )
    (net (code "8") (name "/LCD_BL") (class "Default")
      (node (ref "GND") (pin "41") (pinfunction "PF0(ADC0)_41") (pintype "bidirectional"))
      (node (ref "R19") (pin "2") (pinfunction "2_2") (pintype "passive"))
      (node (ref "TP5") (pin "P$1") (pinfunction "1_P$1") (pintype "bidirectional"))
      (node (ref "U$3") (pin "41") (pinfunction "PF0(ADC0)_41") (pintype "bidirectional"))
    )
    (net (code "9") (name "/LCD_CS") (class "Default")
      (node (ref "GND") (pin "40") (pinfunction "PF1(ADC1)_40") (pintype "bidirectional"))
      (node (ref "U$3") (pin "40") (pinfunction "PF1(ADC1)_40") (pintype "bidirectional"))
      (node (ref "X1") (pin "10") (pinfunction "1_10") (pintype "passive"))
    )
    (net (code "10") (name "/LCD_RST") (class "Default")
      (node (ref "GND") (pin "39") (pinfunction "PF4(ADC4)_39") (pintype "bidirectional"))
      (node (ref "U$3") (pin "39") (pinfunction "PF4(ADC4)_39") (pintype "bidirectional"))
      (node (ref "X1") (pin "9") (pinfunction "1_9") (pintype "passive"))
    )
    (net (code "11") (name "/MISO") (class "Default")
      (node (ref "GND") (pin "11") (pinfunction "PB3(MISO)_11") (pintype "bidirectional"))
      (node (ref "ICSP") (pin "1") (pinfunction "1_1") (pintype "bidirectional"))
      (node (ref "J1") (pin "7") (pinfunction "DO_7") (pintype "bidirectional"))
      (node (ref "U$3") (pin "11") (pinfunction "PB3(MISO)_11") (pintype "bidirectional"))
      (node (ref "U$4") (pin "2") (pinfunction "DO_2") (pintype "bidirectional"))
    )
    (net (code "12") (name "/MOSI") (class "Default")
      (node (ref "GND") (pin "10") (pinfunction "PB2(MOSI)_10") (pintype "bidirectional"))
      (node (ref "ICSP") (pin "4") (pinfunction "4_4") (pintype "bidirectional"))
      (node (ref "J1") (pin "3") (pinfunction "DI_3") (pintype "bidirectional"))
      (node (ref "U$3") (pin "10") (pinfunction "PB2(MOSI)_10") (pintype "bidirectional"))
      (node (ref "U$4") (pin "5") (pinfunction "DI_5") (pintype "bidirectional"))
      (node (ref "X1") (pin "6") (pinfunction "1_6") (pintype "passive"))
    )
    (net (code "13") (name "/PWR_ONOFF") (class "Default")
      (node (ref "GND") (pin "22") (pinfunction "PD5_22") (pintype "bidirectional"))
      (node (ref "Q4") (pin "1") (pinfunction "G_1") (pintype "passive"))
      (node (ref "R22") (pin "1") (pinfunction "1_1") (pintype "passive"))
      (node (ref "TP1") (pin "P$1") (pinfunction "1_P$1") (pintype "bidirectional"))
      (node (ref "U$3") (pin "22") (pinfunction "PD5_22") (pintype "bidirectional"))
    )
    (net (code "14") (name "/RESET") (class "Default")
      (node (ref "GND") (pin "13") (pinfunction "~{RESET}_13") (pintype "bidirectional"))
      (node (ref "ICSP") (pin "5") (pinfunction "5_5") (pintype "bidirectional"))
      (node (ref "R4") (pin "1") (pinfunction "1_1") (pintype "passive"))
      (node (ref "U$3") (pin "13") (pinfunction "~{RESET}_13") (pintype "bidirectional"))
    )
    (net (code "15") (name "/RTC_BATT") (class "Default")
      (node (ref "BAT1") (pin "PWR@1") (pinfunction "+_PWR@1") (pintype "power_in"))
      (node (ref "U$14") (pin "6") (pinfunction "VBAT_6") (pintype "input"))
    )
    (net (code "16") (name "/RTC_INT") (class "Default")
      (node (ref "GND") (pin "20") (pinfunction "PD2(RX)_20") (pintype "bidirectional"))
      (node (ref "R2") (pin "2") (pinfunction "2_2") (pintype "passive"))
      (node (ref "U$14") (pin "3") (pinfunction "INT/SQW_3") (pintype "output"))
      (node (ref "U$3") (pin "20") (pinfunction "PD2(RX)_20") (pintype "bidirectional"))
    )
    (net (code "17") (name "/RXLED") (class "Default")
      (node (ref "GND") (pin "8") (pinfunction "PB0(SS)_8") (pintype "bidirectional"))
      (node (ref "U$3") (pin "8") (pinfunction "PB0(SS)_8") (pintype "bidirectional"))
    )
    (net (code "18") (name "/SCK") (class "Default")
      (node (ref "GND") (pin "9") (pinfunction "PB1(SCK)_9") (pintype "bidirectional"))
      (node (ref "ICSP") (pin "3") (pinfunction "3_3") (pintype "bidirectional"))
      (node (ref "J1") (pin "5") (pinfunction "SCLK_5") (pintype "bidirectional"))
      (node (ref "U$3") (pin "9") (pinfunction "PB1(SCK)_9") (pintype "bidirectional"))
      (node (ref "U$4") (pin "6") (pinfunction "CLK_6") (pintype "bidirectional"))
      (node (ref "X1") (pin "7") (pinfunction "1_7") (pintype "passive"))
    )
    (net (code "19") (name "/SCL") (class "Default")
      (node (ref "GND") (pin "18") (pinfunction "PD0(SCL)_18") (pintype "bidirectional"))
      (node (ref "IC1") (pin "8") (pinfunction "SCL_8") (pintype "input"))
      (node (ref "ICSP1") (pin "1") (pinfunction "1_1") (pintype "bidirectional"))
      (node (ref "R14") (pin "1") (pinfunction "1_1") (pintype "passive"))
      (node (ref "U$14") (pin "8") (pinfunction "SCL_8") (pintype "input"))
      (node (ref "U$3") (pin "18") (pinfunction "PD0(SCL)_18") (pintype "bidirectional"))
      (node (ref "U1") (pin "4") (pinfunction "4_4") (pintype "bidirectional"))
    )
    (net (code "20") (name "/SDA") (class "Default")
      (node (ref "GND") (pin "19") (pinfunction "PD1(SDA)_19") (pintype "bidirectional"))
      (node (ref "IC1") (pin "7") (pinfunction "SDA_7") (pintype "bidirectional"))
      (node (ref "ICSP1") (pin "2") (pinfunction "2_2") (pintype "bidirectional"))
      (node (ref "R13") (pin "1") (pinfunction "1_1") (pintype "passive"))
      (node (ref "U$14") (pin "7") (pinfunction "SDA_7") (pintype "bidirectional"))
      (node (ref "U$3") (pin "19") (pinfunction "PD1(SDA)_19") (pintype "bidirectional"))
      (node (ref "U1") (pin "5") (pinfunction "5_5") (pintype "bidirectional"))
    )
    (net (code "21") (name "/SD_CS") (class "Default")
      (node (ref "GND") (pin "31") (pinfunction "PC6_31") (pintype "bidirectional"))
      (node (ref "J1") (pin "2") (pinfunction "CS_2") (pintype "bidirectional"))
      (node (ref "TP7") (pin "P$1") (pinfunction "1_P$1") (pintype "bidirectional"))
      (node (ref "U$3") (pin "31") (pinfunction "PC6_31") (pintype "bidirectional"))
    )
    (net (code "22") (name "/SW_PWR") (class "Default")
      (node (ref "GND") (pin "12") (pinfunction "PB7_12") (pintype "bidirectional"))
      (node (ref "Q5") (pin "3") (pinfunction "D_3") (pintype "passive"))
      (node (ref "R18") (pin "1") (pinfunction "1_1") (pintype "passive"))
      (node (ref "TP9") (pin "P$1") (pinfunction "1_P$1") (pintype "bidirectional"))
      (node (ref "U$3") (pin "12") (pinfunction "PB7_12") (pintype "bidirectional"))
    )
    (net (code "23") (name "/TC1+") (class "Default")
      (node (ref "C10") (pin "1") (pinfunction "1_1") (pintype "passive"))
      (node (ref "C16") (pin "1") (pinfunction "1_1") (pintype "passive"))
      (node (ref "IC1") (pin "3") (pinfunction "CH2+_3") (pintype "input"))
      (node (ref "R39") (pin "1") (pinfunction "1_1") (pintype "passive"))
    )
    (net (code "24") (name "/TC1-") (class "Default")
      (node (ref "C10") (pin "2") (pinfunction "2_2") (pintype "passive"))
      (node (ref "C15") (pin "1") (pinfunction "1_1") (pintype "passive"))
      (node (ref "IC1") (pin "4") (pinfunction "CH2-_4") (pintype "input"))
      (node (ref "R41") (pin "2") (pinfunction "2_2") (pintype "passive"))
    )
    (net (code "25") (name "/TC2+") (class "Default")
      (node (ref "C11") (pin "1") (pinfunction "1_1") (pintype "passive"))
      (node (ref "C14") (pin "1") (pinfunction "1_1") (pintype "passive"))
      (node (ref "IC1") (pin "1") (pinfunction "CH1+_1") (pintype "input"))
      (node (ref "R40") (pin "1") (pinfunction "1_1") (pintype "passive"))
    )
    (net (code "26") (name "/TC2-") (class "Default")
      (node (ref "C11") (pin "2") (pinfunction "2_2") (pintype "passive"))
      (node (ref "C13") (pin "1") (pinfunction "1_1") (pintype "passive"))
      (node (ref "IC1") (pin "2") (pinfunction "CH1-_2") (pintype "input"))
      (node (ref "R42") (pin "2") (pinfunction "2_2") (pintype "passive"))
    )
    (net (code "27") (name "/TC3+") (class "Default")
      (node (ref "C17") (pin "2") (pinfunction "2_2") (pintype "passive"))
      (node (ref "C7") (pin "1") (pinfunction "1_1") (pintype "passive"))
      (node (ref "IC1") (pin "13") (pinfunction "CH4+_13") (pintype "input"))
      (node (ref "R35") (pin "1") (pinfunction "1_1") (pintype "passive"))
    )
    (net (code "28") (name "/TC3-") (class "Default")
      (node (ref "C24") (pin "2") (pinfunction "2_2") (pintype "passive"))
      (node (ref "C7") (pin "2") (pinfunction "2_2") (pintype "passive"))
      (node (ref "IC1") (pin "14") (pinfunction "CH4-_14") (pintype "input"))
      (node (ref "R36") (pin "2") (pinfunction "2_2") (pintype "passive"))
    )
    (net (code "29") (name "/TC4+") (class "Default")
      (node (ref "C25") (pin "2") (pinfunction "2_2") (pintype "passive"))
      (node (ref "C8") (pin "1") (pinfunction "1_1") (pintype "passive"))
      (node (ref "IC1") (pin "11") (pinfunction "CH3+_11") (pintype "input"))
      (node (ref "R37") (pin "1") (pinfunction "1_1") (pintype "passive"))
    )
    (net (code "30") (name "/TC4-") (class "Default")
      (node (ref "C37") (pin "2") (pinfunction "2_2") (pintype "passive"))
      (node (ref "C8") (pin "2") (pinfunction "2_2") (pintype "passive"))
      (node (ref "IC1") (pin "12") (pinfunction "CH3-_12") (pintype "input"))
      (node (ref "R38") (pin "2") (pinfunction "2_2") (pintype "passive"))
    )
    (net (code "31") (name "/VBAT") (class "Default")
      (node (ref "C9") (pin "1") (pinfunction "1_1") (pintype "passive"))
      (node (ref "Q1") (pin "3") (pinfunction "D_3") (pintype "passive"))
      (node (ref "Q2") (pin "2") (pinfunction "S_2") (pintype "passive"))
      (node (ref "R5") (pin "1") (pinfunction "1_1") (pintype "passive"))
      (node (ref "SJ1") (pin "1") (pinfunction "1_1") (pintype "passive"))
      (node (ref "TP14") (pin "P$1") (pinfunction "1_P$1") (pintype "bidirectional"))
      (node (ref "U3") (pin "3") (pinfunction "VBAT_3") (pintype "power_in"))
    )
    (net (code "32") (name "/VBAT_EN") (class "Default")
      (node (ref "GND") (pin "25") (pinfunction "PD4(ADC8)_25") (pintype "bidirectional"))
      (node (ref "Q3") (pin "1") (pinfunction "G_1") (pintype "passive"))
      (node (ref "R23") (pin "2") (pinfunction "2_2") (pintype "passive"))
      (node (ref "U$3") (pin "25") (pinfunction "PD4(ADC8)_25") (pintype "bidirectional"))
    )
    (net (code "33") (name "/VBAT_SENSE") (class "Default")
      (node (ref "C23") (pin "1") (pinfunction "1_1") (pintype "passive"))
      (node (ref "GND") (pin "26") (pinfunction "PD6(ADC9)_26") (pintype "bidirectional"))
      (node (ref "R20") (pin "1") (pinfunction "1_1") (pintype "passive"))
      (node (ref "R24") (pin "1") (pinfunction "1_1") (pintype "passive"))
      (node (ref "TP4") (pin "P$1") (pinfunction "1_P$1") (pintype "bidirectional"))
      (node (ref "U$3") (pin "26") (pinfunction "PD6(ADC9)_26") (pintype "bidirectional"))
    )
    (net (code "34") (name "/VBUS") (class "Default")
      (node (ref "C1") (pin "1") (pinfunction "1_1") (pintype "passive"))
      (node (ref "C12") (pin "1") (pinfunction "1_1") (pintype "passive"))
      (node (ref "C2") (pin "1") (pinfunction "1_1") (pintype "passive"))
      (node (ref "C28") (pin "1") (pinfunction "1_1") (pintype "passive"))
      (node (ref "D2") (pin "C") (pinfunction "C_C") (pintype "passive"))
      (node (ref "IC3") (pin "8") (pinfunction "VCC_8") (pintype "power_in"))
      (node (ref "JP1") (pin "1") (pinfunction "1_1") (pintype "passive"))
      (node (ref "Q1") (pin "2") (pinfunction "S_2") (pintype "passive"))
      (node (ref "R6") (pin "1") (pinfunction "1_1") (pintype "passive"))
      (node (ref "R7") (pin "1") (pinfunction "1_1") (pintype "passive"))
      (node (ref "TP12") (pin "P$1") (pinfunction "1_P$1") (pintype "bidirectional"))
      (node (ref "U4") (pin "1") (pinfunction "IN_1") (pintype "input"))
    )
    (net (code "35") (name "/VBUS_IN") (class "Default")
      (node (ref "C6") (pin "1") (pinfunction "1_1") (pintype "passive"))
      (node (ref "D2") (pin "A") (pinfunction "A_A") (pintype "passive"))
      (node (ref "GND") (pin "7") (pinfunction "VBUS_7") (pintype "bidirectional"))
      (node (ref "ICSP") (pin "2") (pinfunction "2_2") (pintype "bidirectional"))
      (node (ref "R25") (pin "2") (pinfunction "2_2") (pintype "passive"))
      (node (ref "TP11") (pin "P$1") (pinfunction "1_P$1") (pintype "bidirectional"))
      (node (ref "U$1") (pin "PIN$1") (pinfunction "VCC_PIN$1") (pintype "bidirectional"))
      (node (ref "U$3") (pin "7") (pinfunction "VBUS_7") (pintype "bidirectional"))
      (node (ref "U2") (pin "3") (pinfunction "VCC_3") (pintype "power_in"))
      (node (ref "U3") (pin "4") (pinfunction "VIN_4") (pintype "power_in"))
    )
    (net (code "36") (name "/XTAL1") (class "Default")
      (node (ref "GND") (pin "17") (pinfunction "XTAL1_17") (pintype "bidirectional"))
      (node (ref "U$3") (pin "17") (pinfunction "XTAL1_17") (pintype "bidirectional"))
      (node (ref "Y1") (pin "1") (pinfunction "1_1") (pintype "passive"))
    )
    (net (code "37") (name "/XTAL2") (class "Default")
      (node (ref "GND") (pin "16") (pinfunction "XTAL2_16") (pintype "bidirectional"))
      (node (ref "U$3") (pin "16") (pinfunction "XTAL2_16") (pintype "bidirectional"))
      (node (ref "Y1") (pin "3") (pinfunction "3_3") (pintype "passive"))
    )
    (net (code "38") (name "3.3V") (class "Default")
      (node (ref "C18") (pin "1") (pinfunction "1_1") (pintype "passive"))
      (node (ref "C19") (pin "1") (pinfunction "1_1") (pintype "passive"))
      (node (ref "C20") (pin "2") (pinfunction "2_2") (pintype "passive"))
      (node (ref "C21") (pin "2") (pinfunction "2_2") (pintype "passive"))
      (node (ref "C26") (pin "1") (pinfunction "1_1") (pintype "passive"))
      (node (ref "C27") (pin "1") (pinfunction "1_1") (pintype "passive"))
      (node (ref "C29") (pin "1") (pinfunction "1_1") (pintype "passive"))
      (node (ref "C30") (pin "1") (pinfunction "1_1") (pintype "passive"))
      (node (ref "C31") (pin "1") (pinfunction "1_1") (pintype "passive"))
      (node (ref "C32") (pin "1") (pinfunction "1_1") (pintype "passive"))
      (node (ref "C33") (pin "1") (pinfunction "1_1") (pintype "passive"))
      (node (ref "C34") (pin "1") (pinfunction "1_1") (pintype "passive"))
      (node (ref "C5") (pin "1") (pinfunction "1_1") (pintype "passive"))
      (node (ref "GND") (pin "14") (pinfunction "VCC_14") (pintype "bidirectional"))
      (node (ref "GND") (pin "24") (pinfunction "AVCC_24") (pintype "bidirectional"))
      (node (ref "GND") (pin "34") (pinfunction "VCC_34") (pintype "bidirectional"))
      (node (ref "GND") (pin "44") (pinfunction "AVCC_44") (pintype "bidirectional"))
      (node (ref "GND") (pin "6") (pinfunction "UCAP_6") (pintype "bidirectional"))
      (node (ref "IC1") (pin "6") (pinfunction "VDD_6") (pintype "power_in"))
      (node (ref "ICSP1") (pin "6") (pinfunction "6_6") (pintype "bidirectional"))
      (node (ref "J1") (pin "4") (pinfunction "VDD_4") (pintype "bidirectional"))
      (node (ref "Q5") (pin "2") (pinfunction "S_2") (pintype "passive"))
      (node (ref "R1") (pin "1") (pinfunction "1_1") (pintype "passive"))
      (node (ref "R11") (pin "1") (pinfunction "1_1") (pintype "passive"))
      (node (ref "R12") (pin "1") (pinfunction "1_1") (pintype "passive"))
      (node (ref "R13") (pin "2") (pinfunction "2_2") (pintype "passive"))
      (node (ref "R14") (pin "2") (pinfunction "2_2") (pintype "passive"))
      (node (ref "R15") (pin "1") (pinfunction "1_1") (pintype "passive"))
      (node (ref "R16") (pin "1") (pinfunction "1_1") (pintype "passive"))
      (node (ref "R2") (pin "1") (pinfunction "1_1") (pintype "passive"))
      (node (ref "R27") (pin "2") (pinfunction "2_2") (pintype "passive"))
      (node (ref "R28") (pin "2") (pinfunction "2_2") (pintype "passive"))
      (node (ref "R29") (pin "2") (pinfunction "2_2") (pintype "passive"))
      (node (ref "R30") (pin "2") (pinfunction "2_2") (pintype "passive"))
      (node (ref "R4") (pin "2") (pinfunction "2_2") (pintype "passive"))
      (node (ref "R8") (pin "1") (pinfunction "1_1") (pintype "passive"))
      (node (ref "TP13") (pin "P$1") (pinfunction "1_P$1") (pintype "bidirectional"))
      (node (ref "U$14") (pin "2") (pinfunction "VCC_2") (pintype "power_in"))
      (node (ref "U$3") (pin "14") (pinfunction "VCC_14") (pintype "bidirectional"))
      (node (ref "U$3") (pin "24") (pinfunction "AVCC_24") (pintype "bidirectional"))
      (node (ref "U$3") (pin "34") (pinfunction "VCC_34") (pintype "bidirectional"))
      (node (ref "U$3") (pin "44") (pinfunction "AVCC_44") (pintype "bidirectional"))
      (node (ref "U$3") (pin "6") (pinfunction "UCAP_6") (pintype "bidirectional"))
      (node (ref "U$4") (pin "3") (pinfunction "~{WP}_3") (pintype "bidirectional"))
      (node (ref "U$4") (pin "7") (pinfunction "~{HOLD}_7") (pintype "bidirectional"))
      (node (ref "U$4") (pin "8") (pinfunction "VCC_8") (pintype "bidirectional"))
      (node (ref "U1") (pin "1") (pinfunction "1_1") (pintype "bidirectional"))
      (node (ref "U4") (pin "5") (pinfunction "OUT_5") (pintype "passive"))
      (node (ref "X1") (pin "12") (pinfunction "1_12") (pintype "passive"))
      (node (ref "X1") (pin "5") (pinfunction "1_5") (pintype "passive"))
    )
    (net (code "39") (name "D+") (class "Default")
      (node (ref "GND") (pin "4") (pinfunction "D+_4") (pintype "bidirectional"))
      (node (ref "R9") (pin "2") (pinfunction "2_2") (pintype "passive"))
      (node (ref "U$3") (pin "4") (pinfunction "D+_4") (pintype "bidirectional"))
    )
    (net (code "40") (name "D-") (class "Default")
      (node (ref "GND") (pin "3") (pinfunction "D-_3") (pintype "bidirectional"))
      (node (ref "R10") (pin "2") (pinfunction "2_2") (pintype "passive"))
      (node (ref "U$3") (pin "3") (pinfunction "D-_3") (pintype "bidirectional"))
    )
    (net (code "41") (name "GND") (class "Default")
      (node (ref "BAT1") (pin "GND") (pinfunction "-_GND") (pintype "power_in"))
      (node (ref "C1") (pin "2") (pinfunction "2_2") (pintype "passive"))
      (node (ref "C12") (pin "2") (pinfunction "2_2") (pintype "passive"))
      (node (ref "C18") (pin "2") (pinfunction "2_2") (pintype "passive"))
      (node (ref "C19") (pin "2") (pinfunction "2_2") (pintype "passive"))
      (node (ref "C2") (pin "2") (pinfunction "2_2") (pintype "passive"))
      (node (ref "C20") (pin "1") (pinfunction "1_1") (pintype "passive"))
      (node (ref "C21") (pin "1") (pinfunction "1_1") (pintype "passive"))
      (node (ref "C22") (pin "2") (pinfunction "2_2") (pintype "passive"))
      (node (ref "C23") (pin "2") (pinfunction "2_2") (pintype "passive"))
      (node (ref "C26") (pin "2") (pinfunction "2_2") (pintype "passive"))
      (node (ref "C27") (pin "2") (pinfunction "2_2") (pintype "passive"))
      (node (ref "C28") (pin "2") (pinfunction "2_2") (pintype "passive"))
      (node (ref "C29") (pin "2") (pinfunction "2_2") (pintype "passive"))
      (node (ref "C3") (pin "2") (pinfunction "2_2") (pintype "passive"))
      (node (ref "C30") (pin "2") (pinfunction "2_2") (pintype "passive"))
      (node (ref "C32") (pin "2") (pinfunction "2_2") (pintype "passive"))
      (node (ref "C33") (pin "2") (pinfunction "2_2") (pintype "passive"))
      (node (ref "C34") (pin "2") (pinfunction "2_2") (pintype "passive"))
      (node (ref "C36") (pin "1") (pinfunction "1_1") (pintype "passive"))
      (node (ref "C4") (pin "2") (pinfunction "2_2") (pintype "passive"))
      (node (ref "C5") (pin "2") (pinfunction "2_2") (pintype "passive"))
      (node (ref "C6") (pin "2") (pinfunction "2_2") (pintype "passive"))
      (node (ref "C9") (pin "2") (pinfunction "2_2") (pintype "passive"))
      (node (ref "GND") (pin "15") (pinfunction "GND_15") (pintype "bidirectional"))
      (node (ref "GND") (pin "23") (pinfunction "GND_23") (pintype "bidirectional"))
      (node (ref "GND") (pin "33") (pinfunction "PE2/~{HWB}_33") (pintype "bidirectional"))
      (node (ref "GND") (pin "35") (pinfunction "GND_35") (pintype "bidirectional"))
      (node (ref "GND") (pin "43") (pinfunction "GND_43") (pintype "bidirectional"))
      (node (ref "GND") (pin "5") (pinfunction "UGND_5") (pintype "bidirectional"))
      (node (ref "GND") (pin "P$1") (pinfunction "GND_PAD_P$1") (pintype "bidirectional"))
      (node (ref "IC1") (pin "5") (pinfunction "GND_5") (pintype "power_in"))
      (node (ref "IC1") (pin "9") (pinfunction "A0_9") (pintype "input"))
      (node (ref "IC3") (pin "1") (pinfunction "CLK_1") (pintype "input"))
      (node (ref "IC3") (pin "2") (pinfunction "D_2") (pintype "input"))
      (node (ref "IC3") (pin "4") (pinfunction "GND_4") (pintype "power_in"))
      (node (ref "ICSP") (pin "6") (pinfunction "6_6") (pintype "bidirectional"))
      (node (ref "ICSP1") (pin "5") (pinfunction "5_5") (pintype "bidirectional"))
      (node (ref "J1") (pin "6") (pinfunction "VSS_6") (pintype "bidirectional"))
      (node (ref "J1") (pin "G1") (pinfunction "G1_G1") (pintype "bidirectional"))
      (node (ref "J1") (pin "G2") (pinfunction "G2_G2") (pintype "bidirectional"))
      (node (ref "J1") (pin "G3") (pinfunction "G3_G3") (pintype "bidirectional"))
      (node (ref "J1") (pin "G4") (pinfunction "G4_G4") (pintype "bidirectional"))
      (node (ref "Q3") (pin "2") (pinfunction "S_2") (pintype "passive"))
      (node (ref "Q4") (pin "2") (pinfunction "S_2") (pintype "passive"))
      (node (ref "R18") (pin "2") (pinfunction "2_2") (pintype "passive"))
      (node (ref "R22") (pin "2") (pinfunction "2_2") (pintype "passive"))
      (node (ref "R23") (pin "1") (pinfunction "1_1") (pintype "passive"))
      (node (ref "R24") (pin "2") (pinfunction "2_2") (pintype "passive"))
      (node (ref "R25") (pin "1") (pinfunction "1_1") (pintype "passive"))
      (node (ref "R3") (pin "2") (pinfunction "2_2") (pintype "passive"))
      (node (ref "S1") (pin "1") (pinfunction "1_1") (pintype "passive"))
      (node (ref "S2") (pin "1") (pinfunction "1_1") (pintype "passive"))
      (node (ref "S3") (pin "1") (pinfunction "1_1") (pintype "passive"))
      (node (ref "S4") (pin "1") (pinfunction "1_1") (pintype "passive"))
      (node (ref "S5") (pin "1") (pinfunction "1_1") (pintype "passive"))
      (node (ref "S6") (pin "3") (pinfunction "2_3") (pintype "passive"))
      (node (ref "SJ2") (pin "1") (pinfunction "1_1") (pintype "passive"))
      (node (ref "TP15") (pin "P$1") (pinfunction "1_P$1") (pintype "bidirectional"))
      (node (ref "U$1") (pin "PAD$1") (pinfunction "SHIELD_PAD$1") (pintype "bidirectional"))
      (node (ref "U$1") (pin "PAD$10") (pinfunction "SHIELD_PAD$10") (pintype "bidirectional"))
      (node (ref "U$1") (pin "PAD$2") (pinfunction "SHIELD_PAD$2") (pintype "bidirectional"))
      (node (ref "U$1") (pin "PAD$3") (pinfunction "SHIELD_PAD$3") (pintype "bidirectional"))
      (node (ref "U$1") (pin "PAD$4") (pinfunction "SHIELD_PAD$4") (pintype "bidirectional"))
      (node (ref "U$1") (pin "PAD$5") (pinfunction "SHIELD_PAD$5") (pintype "bidirectional"))
      (node (ref "U$1") (pin "PAD$6") (pinfunction "SHIELD_PAD$6") (pintype "bidirectional"))
      (node (ref "U$1") (pin "PAD$7") (pinfunction "SHIELD_PAD$7") (pintype "bidirectional"))
      (node (ref "U$1") (pin "PAD$8") (pinfunction "SHIELD_PAD$8") (pintype "bidirectional"))
      (node (ref "U$1") (pin "PAD$9") (pinfunction "SHIELD_PAD$9") (pintype "bidirectional"))
      (node (ref "U$1") (pin "PIN$5") (pinfunction "GND_PIN$5") (pintype "bidirectional"))
      (node (ref "U$14") (pin "5") (pinfunction "GND_5") (pintype "power_in"))
      (node (ref "U$2") (pin "P$3") (pinfunction "GND_P$3") (pintype "bidirectional"))
      (node (ref "U$2") (pin "P$4") (pinfunction "P$4_P$4") (pintype "bidirectional"))
      (node (ref "U$2") (pin "P$5") (pinfunction "P$5_P$5") (pintype "bidirectional"))
      (node (ref "U$3") (pin "15") (pinfunction "GND_15") (pintype "bidirectional"))
      (node (ref "U$3") (pin "23") (pinfunction "GND_23") (pintype "bidirectional"))
      (node (ref "U$3") (pin "33") (pinfunction "PE2/~{HWB}_33") (pintype "bidirectional"))
      (node (ref "U$3") (pin "35") (pinfunction "GND_35") (pintype "bidirectional"))
      (node (ref "U$3") (pin "43") (pinfunction "GND_43") (pintype "bidirectional"))
      (node (ref "U$3") (pin "5") (pinfunction "UGND_5") (pintype "bidirectional"))
      (node (ref "U$4") (pin "4") (pinfunction "GND_4") (pintype "bidirectional"))
      (node (ref "U2") (pin "1") (pinfunction "GND_1") (pintype "power_in"))
      (node (ref "U3") (pin "2") (pinfunction "VSS_2") (pintype "power_in"))
      (node (ref "U4") (pin "2") (pinfunction "GND_2") (pintype "input"))
      (node (ref "X1") (pin "4") (pinfunction "1_4") (pintype "passive"))
      (node (ref "Y1") (pin "2") (pinfunction "2_2") (pintype "passive"))
      (node (ref "Z1") (pin "1") (pinfunction "1_1") (pintype "passive"))
      (node (ref "Z2") (pin "1") (pinfunction "1_1") (pintype "passive"))
    )
    (net (code "42") (name "Net-(C36-Pad2)") (class "Default")
      (node (ref "C36") (pin "2") (pinfunction "2_2") (pintype "passive"))
      (node (ref "X1") (pin "1") (pinfunction "1_1") (pintype "passive"))
    )
    (net (code "43") (name "Net-(GND-AREF)") (class "Default")
      (node (ref "C3") (pin "1") (pinfunction "1_1") (pintype "passive"))
      (node (ref "GND") (pin "42") (pinfunction "AREF_42") (pintype "bidirectional"))
      (node (ref "U$3") (pin "42") (pinfunction "AREF_42") (pintype "bidirectional"))
    )
    (net (code "44") (name "Net-(GND-UVCC)") (class "Default")
      (node (ref "GND") (pin "2") (pinfunction "UVCC_2") (pintype "bidirectional"))
      (node (ref "U$3") (pin "2") (pinfunction "UVCC_2") (pintype "bidirectional"))
    )
    (net (code "45") (name "Net-(IC3-Q)") (class "Default")
      (node (ref "IC3") (pin "5") (pinfunction "Q_5") (pintype "output"))
      (node (ref "R21") (pin "1") (pinfunction "1_1") (pintype "passive"))
    )
    (net (code "46") (name "Net-(IC3-~{CLR})") (class "Default")
      (node (ref "IC3") (pin "6") (pinfunction "~{CLR}_6") (pintype "input"))
      (node (ref "Q4") (pin "3") (pinfunction "D_3") (pintype "passive"))
      (node (ref "R7") (pin "2") (pinfunction "2_2") (pintype "passive"))
    )
    (net (code "47") (name "Net-(IC3-~{SET})") (class "Default")
      (node (ref "IC3") (pin "7") (pinfunction "~{SET}_7") (pintype "input"))
      (node (ref "Q5") (pin "1") (pinfunction "G_1") (pintype "passive"))
      (node (ref "R6") (pin "2") (pinfunction "2_2") (pintype "passive"))
      (node (ref "S6") (pin "1") (pinfunction "1_1") (pintype "passive"))
    )
    (net (code "48") (name "Net-(Q1-G)") (class "Default")
      (node (ref "Q1") (pin "1") (pinfunction "G_1") (pintype "passive"))
      (node (ref "U2") (pin "2") (pinfunction "~{RST}_2") (pintype "bidirectional"))
    )
    (net (code "49") (name "Net-(Q2-D)") (class "Default")
      (node (ref "Q2") (pin "3") (pinfunction "D_3") (pintype "passive"))
      (node (ref "R20") (pin "2") (pinfunction "2_2") (pintype "passive"))
    )
    (net (code "50") (name "Net-(Q2-G)") (class "Default")
      (node (ref "Q2") (pin "1") (pinfunction "G_1") (pintype "passive"))
      (node (ref "Q3") (pin "3") (pinfunction "D_3") (pintype "passive"))
      (node (ref "R5") (pin "2") (pinfunction "2_2") (pintype "passive"))
    )
    (net (code "51") (name "Net-(U$1-D+)") (class "Default")
      (node (ref "R9") (pin "1") (pinfunction "1_1") (pintype "passive"))
      (node (ref "U$1") (pin "PIN$3") (pinfunction "D+_PIN$3") (pintype "bidirectional"))
      (node (ref "Z1") (pin "2") (pinfunction "2_2") (pintype "passive"))
    )
    (net (code "52") (name "Net-(U$1-D-)") (class "Default")
      (node (ref "R10") (pin "1") (pinfunction "1_1") (pintype "passive"))
      (node (ref "U$1") (pin "PIN$2") (pinfunction "D-_PIN$2") (pintype "bidirectional"))
      (node (ref "Z2") (pin "2") (pinfunction "2_2") (pintype "passive"))
    )
    (net (code "53") (name "Net-(U$2-VBAT)") (class "Default")
      (node (ref "SJ1") (pin "2") (pinfunction "2_2") (pintype "passive"))
      (node (ref "U$2") (pin "P$1") (pinfunction "VBAT_P$1") (pintype "bidirectional"))
    )
    (net (code "54") (name "Net-(U$7-1)") (class "Default")
      (node (ref "R27") (pin "1") (pinfunction "1_1") (pintype "passive"))
      (node (ref "R35") (pin "2") (pinfunction "2_2") (pintype "passive"))
      (node (ref "U$7") (pin "P$1") (pinfunction "1_P$1") (pintype "passive"))
    )
    (net (code "55") (name "Net-(U$8-1)") (class "Default")
      (node (ref "R31") (pin "2") (pinfunction "2_2") (pintype "passive"))
      (node (ref "R36") (pin "1") (pinfunction "1_1") (pintype "passive"))
      (node (ref "U$8") (pin "P$1") (pinfunction "1_P$1") (pintype "passive"))
    )
    (net (code "56") (name "Net-(U$9-1)") (class "Default")
      (node (ref "R28") (pin "1") (pinfunction "1_1") (pintype "passive"))
      (node (ref "R37") (pin "2") (pinfunction "2_2") (pintype "passive"))
      (node (ref "U$9") (pin "P$1") (pinfunction "1_P$1") (pintype "passive"))
    )
    (net (code "57") (name "Net-(U$15-1)") (class "Default")
      (node (ref "R32") (pin "2") (pinfunction "2_2") (pintype "passive"))
      (node (ref "R38") (pin "1") (pinfunction "1_1") (pintype "passive"))
      (node (ref "U$15") (pin "P$1") (pinfunction "1_P$1") (pintype "passive"))
    )
    (net (code "58") (name "Net-(U$16-1)") (class "Default")
      (node (ref "R29") (pin "1") (pinfunction "1_1") (pintype "passive"))
      (node (ref "R39") (pin "2") (pinfunction "2_2") (pintype "passive"))
      (node (ref "U$16") (pin "P$1") (pinfunction "1_P$1") (pintype "passive"))
    )
    (net (code "59") (name "Net-(U$17-1)") (class "Default")
      (node (ref "R33") (pin "2") (pinfunction "2_2") (pintype "passive"))
      (node (ref "R41") (pin "1") (pinfunction "1_1") (pintype "passive"))
      (node (ref "U$17") (pin "P$1") (pinfunction "1_P$1") (pintype "passive"))
    )
    (net (code "60") (name "Net-(U$18-1)") (class "Default")
      (node (ref "R30") (pin "1") (pinfunction "1_1") (pintype "passive"))
      (node (ref "R40") (pin "2") (pinfunction "2_2") (pintype "passive"))
      (node (ref "U$18") (pin "P$1") (pinfunction "1_P$1") (pintype "passive"))
    )
    (net (code "61") (name "Net-(U$19-1)") (class "Default")
      (node (ref "R34") (pin "2") (pinfunction "2_2") (pintype "passive"))
      (node (ref "R42") (pin "1") (pinfunction "1_1") (pintype "passive"))
      (node (ref "U$19") (pin "P$1") (pinfunction "1_P$1") (pintype "passive"))
    )
    (net (code "62") (name "Net-(U3-PROG)") (class "Default")
      (node (ref "R3") (pin "1") (pinfunction "1_1") (pintype "passive"))
      (node (ref "U3") (pin "5") (pinfunction "PROG_5") (pintype "input"))
    )
    (net (code "63") (name "Net-(U3-STAT)") (class "Default")
      (node (ref "R17") (pin "2") (pinfunction "2_2") (pintype "passive"))
      (node (ref "U3") (pin "1") (pinfunction "STAT_1") (pintype "output"))
    )
    (net (code "64") (name "Net-(U4-BP)") (class "Default")
      (node (ref "C4") (pin "1") (pinfunction "1_1") (pintype "passive"))
      (node (ref "U4") (pin "4") (pinfunction "BP_4") (pintype "input"))
    )
    (net (code "65") (name "Net-(X1C-1)") (class "Default")
      (node (ref "R19") (pin "1") (pinfunction "1_1") (pintype "passive"))
      (node (ref "X1") (pin "11") (pinfunction "1_11") (pintype "passive"))
    )
    (net (code "66") (name "Net-(X1E-1)") (class "Default")
      (node (ref "C35") (pin "2") (pinfunction "2_2") (pintype "passive"))
      (node (ref "X1") (pin "2") (pinfunction "1_2") (pintype "passive"))
    )
    (net (code "67") (name "Net-(X1F-1)") (class "Default")
      (node (ref "C35") (pin "1") (pinfunction "1_1") (pintype "passive"))
      (node (ref "X1") (pin "3") (pinfunction "1_3") (pintype "passive"))
    )
    (net (code "68") (name "SW_A") (class "Default")
      (node (ref "GND") (pin "1") (pinfunction "PE6_1") (pintype "bidirectional"))
      (node (ref "R8") (pin "2") (pinfunction "2_2") (pintype "passive"))
      (node (ref "S3") (pin "3") (pinfunction "2_3") (pintype "passive"))
      (node (ref "U$3") (pin "1") (pinfunction "PE6_1") (pintype "bidirectional"))
    )
    (net (code "69") (name "SW_B") (class "Default")
      (node (ref "GND") (pin "21") (pinfunction "PD3(TX)_21") (pintype "bidirectional"))
      (node (ref "R11") (pin "2") (pinfunction "2_2") (pintype "passive"))
      (node (ref "S2") (pin "3") (pinfunction "2_3") (pintype "passive"))
      (node (ref "U$3") (pin "21") (pinfunction "PD3(TX)_21") (pintype "bidirectional"))
    )
    (net (code "70") (name "SW_C") (class "Default")
      (node (ref "GND") (pin "28") (pinfunction "PB4(ADC11)_28") (pintype "bidirectional"))
      (node (ref "R12") (pin "2") (pinfunction "2_2") (pintype "passive"))
      (node (ref "S1") (pin "3") (pinfunction "2_3") (pintype "passive"))
      (node (ref "U$3") (pin "28") (pinfunction "PB4(ADC11)_28") (pintype "bidirectional"))
    )
    (net (code "71") (name "SW_D") (class "Default")
      (node (ref "GND") (pin "29") (pinfunction "PB5(ADC12)_29") (pintype "bidirectional"))
      (node (ref "R15") (pin "2") (pinfunction "2_2") (pintype "passive"))
      (node (ref "S4") (pin "3") (pinfunction "2_3") (pintype "passive"))
      (node (ref "U$3") (pin "29") (pinfunction "PB5(ADC12)_29") (pintype "bidirectional"))
    )
    (net (code "72") (name "SW_E") (class "Default")
      (node (ref "GND") (pin "30") (pinfunction "PB6(ADC13)_30") (pintype "bidirectional"))
      (node (ref "R16") (pin "2") (pinfunction "2_2") (pintype "passive"))
      (node (ref "S5") (pin "3") (pinfunction "2_3") (pintype "passive"))
      (node (ref "U$3") (pin "30") (pinfunction "PB6(ADC13)_30") (pintype "bidirectional"))
    )
    (net (code "73") (name "unconnected-(IC1-A1-Pad10)") (class "Default")
      (node (ref "IC1") (pin "10") (pinfunction "A1_10") (pintype "input"))
    )
    (net (code "74") (name "unconnected-(IC3-~{Q}-Pad3)") (class "Default")
      (node (ref "IC3") (pin "3") (pinfunction "~{Q}_3") (pintype "output"))
    )
    (net (code "75") (name "unconnected-(J1-CDN-Pad9)") (class "Default")
      (node (ref "J1") (pin "9") (pinfunction "CDN_9") (pintype "bidirectional"))
    )
    (net (code "76") (name "unconnected-(J1-DATA1-Pad8)") (class "Default")
      (node (ref "J1") (pin "8") (pinfunction "DATA1_8") (pintype "bidirectional"))
    )
    (net (code "77") (name "unconnected-(J1-DATA2-Pad1)") (class "Default")
      (node (ref "J1") (pin "1") (pinfunction "DATA2_1") (pintype "bidirectional"))
    )
    (net (code "78") (name "unconnected-(U$1-ID-PadPIN$4)") (class "Default")
      (node (ref "U$1") (pin "PIN$4") (pinfunction "ID_PIN$4") (pintype "bidirectional"))
    )
    (net (code "79") (name "unconnected-(U$2-BSI-PadP$2)") (class "Default")
      (node (ref "U$2") (pin "P$2") (pinfunction "BSI_P$2") (pintype "bidirectional"))
    )
    (net (code "80") (name "unconnected-(U$14-32KHZ-Pad1)") (class "Default")
      (node (ref "U$14") (pin "1") (pinfunction "32KHZ_1") (pintype "output"))
    )
    (net (code "81") (name "unconnected-(U$14-RST-Pad4)") (class "Default")
      (node (ref "U$14") (pin "4") (pinfunction "RST_4") (pintype "bidirectional"))
    )
    (net (code "82") (name "unconnected-(U1-Pad3)") (class "Default")
      (node (ref "U1") (pin "3") (pinfunction "3_3") (pintype "bidirectional"))
    )
  )
)
